# Comparator.net
KiCad netlist of a schematic drawn in Altium Designer
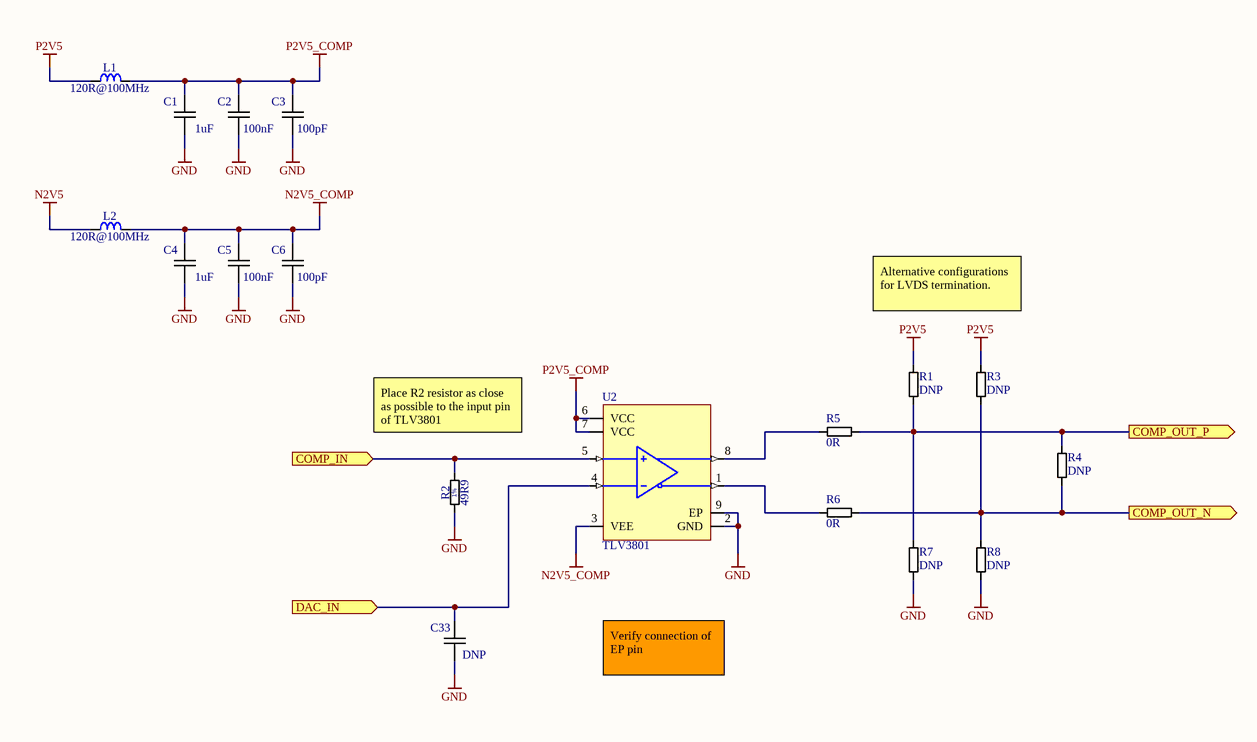
[diagram p0: Comparator.SchDoc]

(export (version "E")
  (design (tool "Eeschema 10.0.6"))
  (components
    (comp (ref "C1")
      (value "1uF")
      (footprint "CAPC0603X90N")
      (description "Non-polarised capacitor")
      (fields (field (name "MANUFACTURER PART NUMBER") "CL10B105KO8NNNC"))
      (libsource (lib "Capacitors") (part "Capacitor - non polarized"))
    )
    (comp (ref "C2")
      (value "100nF")
      (footprint "CAPC0603X90N")
      (description "Non-polarised capacitor")
      (fields (field (name "MANUFACTURER PART NUMBER") "VJ0603Y104KXJCW1BC"))
      (libsource (lib "Capacitors") (part "Capacitor - non polarized"))
    )
    (comp (ref "C3")
      (value "100pF")
      (footprint "CAPC0603X90N")
      (description "Non-polarised capacitor")
      (fields (field (name "MANUFACTURER PART NUMBER") "06035C101JAT2A"))
      (libsource (lib "Capacitors") (part "Capacitor - non polarized"))
    )
    (comp (ref "C4")
      (value "1uF")
      (footprint "CAPC0603X90N")
      (description "Non-polarised capacitor")
      (fields (field (name "MANUFACTURER PART NUMBER") "CL10B105KO8NNNC"))
      (libsource (lib "Capacitors") (part "Capacitor - non polarized"))
    )
    (comp (ref "C5")
      (value "100nF")
      (footprint "CAPC0603X90N")
      (description "Non-polarised capacitor")
      (fields (field (name "MANUFACTURER PART NUMBER") "VJ0603Y104KXJCW1BC"))
      (libsource (lib "Capacitors") (part "Capacitor - non polarized"))
    )
    (comp (ref "C6")
      (value "100pF")
      (footprint "CAPC0603X90N")
      (description "Non-polarised capacitor")
      (fields (field (name "MANUFACTURER PART NUMBER") "06035C101JAT2A"))
      (libsource (lib "Capacitors") (part "Capacitor - non polarized"))
    )
    (comp (ref "C33")
      (value "DNP")
      (footprint "CAPC0603X90N")
      (description "Non-polarised capacitor")
      (fields (field (name "MANUFACTURER PART NUMBER") "UNDEFINED"))
      (libsource (lib "Capacitors") (part "Capacitor - non polarized"))
    )
    (comp (ref "L1")
      (value "120R@100MHz")
      (footprint "INDC0603X90N")
      (description "Ferrite Bead")
      (fields (field (name "MANUFACTURER PART NUMBER") "BLM18PG121SN1D") (field (name "TOLERANCE") "25%"))
      (libsource (lib "Inductors") (part "Inductor"))
    )
    (comp (ref "L2")
      (value "120R@100MHz")
      (footprint "INDC0603X90N")
      (description "Ferrite Bead")
      (fields (field (name "MANUFACTURER PART NUMBER") "BLM18PG121SN1D") (field (name "TOLERANCE") "25%"))
      (libsource (lib "Inductors") (part "Inductor"))
    )
    (comp (ref "R1")
      (value "DNP")
      (footprint "RESC0402X40N")
      (description "General Purpose Thick Film Chip Resistor")
      (fields (field (name "VOLTAGE") "50V"))
      (libsource (lib "Resistors") (part "Resistor - Generic"))
    )
    (comp (ref "R2")
      (value "49R9")
      (footprint "RESC0402X40N")
      (description "General Purpose Thick Film Chip Resistor")
      (fields (field (name "MANUFACTURER PART NUMBER") "RC0402FR-0749R9L") (field (name "TOLERANCE") "1%"))
      (libsource (lib "Resistors") (part "Resistor - 1%"))
    )
    (comp (ref "R3")
      (value "DNP")
      (footprint "RESC0402X40N")
      (description "General Purpose Thick Film Chip Resistor")
      (fields (field (name "VOLTAGE") "50V"))
      (libsource (lib "Resistors") (part "Resistor - Generic"))
    )
    (comp (ref "R4")
      (value "DNP")
      (footprint "RESC0402X40N")
      (description "General Purpose Thick Film Chip Resistor")
      (fields (field (name "VOLTAGE") "50V"))
      (libsource (lib "Resistors") (part "Resistor - Generic"))
    )
    (comp (ref "R5")
      (value "0R")
      (footprint "RESC0402X40N")
      (description "General Purpose Thick Film Chip Resistor")
      (fields
        (field (name "MANUFACTURER PART NUMBER") "CRCW04020000Z0EDC")
        (field (name "TOLERANCE") "20mOhm")
      )
      (libsource (lib "Resistors") (part "Resistor - Generic"))
    )
    (comp (ref "R6")
      (value "0R")
      (footprint "RESC0402X40N")
      (description "General Purpose Thick Film Chip Resistor")
      (fields
        (field (name "MANUFACTURER PART NUMBER") "CRCW04020000Z0EDC")
        (field (name "TOLERANCE") "20mOhm")
      )
      (libsource (lib "Resistors") (part "Resistor - Generic"))
    )
    (comp (ref "R7")
      (value "DNP")
      (footprint "RESC0402X40N")
      (description "General Purpose Thick Film Chip Resistor")
      (fields (field (name "VOLTAGE") "50V"))
      (libsource (lib "Resistors") (part "Resistor - Generic"))
    )
    (comp (ref "R8")
      (value "DNP")
      (footprint "RESC0402X40N")
      (description "General Purpose Thick Film Chip Resistor")
      (fields (field (name "VOLTAGE") "50V"))
      (libsource (lib "Resistors") (part "Resistor - Generic"))
    )
    (comp (ref "U2")
      (value "TLV3801")
      (description "225-ps High-Speed Comparator with LVDS Outputs")
      (fields (field (name "MANUFACTURER PART NUMBER") "TLV3801DSG(_)"))
      (libsource (lib "ICs_and_Semiconductors") (part "TLV3801"))
    )
  )
  (nets
    (net (code "1") (name "/COMP_IN") (class "Default")
      (node (ref "R2") (pin "2") (pinfunction "2_2") (pintype "passive"))
      (node (ref "U2") (pin "5") (pinfunction "IN+_5") (pintype "input"))
    )
    (net (code "2") (name "/COMP_OUT_N") (class "Default")
      (node (ref "R3") (pin "1") (pinfunction "1_1") (pintype "passive"))
      (node (ref "R4") (pin "1") (pinfunction "1_1") (pintype "passive"))
      (node (ref "R6") (pin "2") (pinfunction "2_2") (pintype "passive"))
      (node (ref "R8") (pin "2") (pinfunction "2_2") (pintype "passive"))
    )
    (net (code "3") (name "/COMP_OUT_P") (class "Default")
      (node (ref "R1") (pin "1") (pinfunction "1_1") (pintype "passive"))
      (node (ref "R4") (pin "2") (pinfunction "2_2") (pintype "passive"))
      (node (ref "R5") (pin "2") (pinfunction "2_2") (pintype "passive"))
      (node (ref "R7") (pin "2") (pinfunction "2_2") (pintype "passive"))
    )
    (net (code "4") (name "/DAC_IN") (class "Default")
      (node (ref "C33") (pin "1") (pinfunction "1_1") (pintype "passive"))
      (node (ref "U2") (pin "4") (pinfunction "IN-_4") (pintype "input"))
    )
    (net (code "5") (name "GND") (class "Default")
      (node (ref "C1") (pin "2") (pinfunction "2_2") (pintype "passive"))
      (node (ref "C2") (pin "2") (pinfunction "2_2") (pintype "passive"))
      (node (ref "C3") (pin "2") (pinfunction "2_2") (pintype "passive"))
      (node (ref "C33") (pin "2") (pinfunction "2_2") (pintype "passive"))
      (node (ref "C4") (pin "2") (pinfunction "2_2") (pintype "passive"))
      (node (ref "C5") (pin "2") (pinfunction "2_2") (pintype "passive"))
      (node (ref "C6") (pin "2") (pinfunction "2_2") (pintype "passive"))
      (node (ref "R2") (pin "1") (pinfunction "1_1") (pintype "passive"))
      (node (ref "R7") (pin "1") (pinfunction "1_1") (pintype "passive"))
      (node (ref "R8") (pin "1") (pinfunction "1_1") (pintype "passive"))
      (node (ref "U2") (pin "2") (pinfunction "GND_2") (pintype "power_in"))
      (node (ref "U2") (pin "9") (pinfunction "EP_9") (pintype "power_in"))
    )
    (net (code "6") (name "N2V5") (class "Default")
      (node (ref "L2") (pin "1") (pinfunction "1_1") (pintype "passive"))
    )
    (net (code "7") (name "N2V5_COMP") (class "Default")
      (node (ref "C4") (pin "1") (pinfunction "1_1") (pintype "passive"))
      (node (ref "C5") (pin "1") (pinfunction "1_1") (pintype "passive"))
      (node (ref "C6") (pin "1") (pinfunction "1_1") (pintype "passive"))
      (node (ref "L2") (pin "2") (pinfunction "2_2") (pintype "passive"))
      (node (ref "U2") (pin "3") (pinfunction "VEE_3") (pintype "power_in"))
    )
    (net (code "8") (name "Net-(U2-OUT+)") (class "Default")
      (node (ref "R5") (pin "1") (pinfunction "1_1") (pintype "passive"))
      (node (ref "U2") (pin "8") (pinfunction "OUT+_8") (pintype "output"))
    )
    (net (code "9") (name "Net-(U2-OUT-)") (class "Default")
      (node (ref "R6") (pin "1") (pinfunction "1_1") (pintype "passive"))
      (node (ref "U2") (pin "1") (pinfunction "OUT-_1") (pintype "output"))
    )
    (net (code "10") (name "P2V5") (class "Default")
      (node (ref "L1") (pin "1") (pinfunction "1_1") (pintype "passive"))
      (node (ref "R1") (pin "2") (pinfunction "2_2") (pintype "passive"))
      (node (ref "R3") (pin "2") (pinfunction "2_2") (pintype "passive"))
    )
    (net (code "11") (name "P2V5_COMP") (class "Default")
      (node (ref "C1") (pin "1") (pinfunction "1_1") (pintype "passive"))
      (node (ref "C2") (pin "1") (pinfunction "1_1") (pintype "passive"))
      (node (ref "C3") (pin "1") (pinfunction "1_1") (pintype "passive"))
      (node (ref "L1") (pin "2") (pinfunction "2_2") (pintype "passive"))
      (node (ref "U2") (pin "6") (pinfunction "VCC_6") (pintype "power_in"))
      (node (ref "U2") (pin "7") (pinfunction "VCC_7") (pintype "power_in"))
    )
  )
)
